# Control.net
KiCad netlist of a schematic drawn in Altium Designer
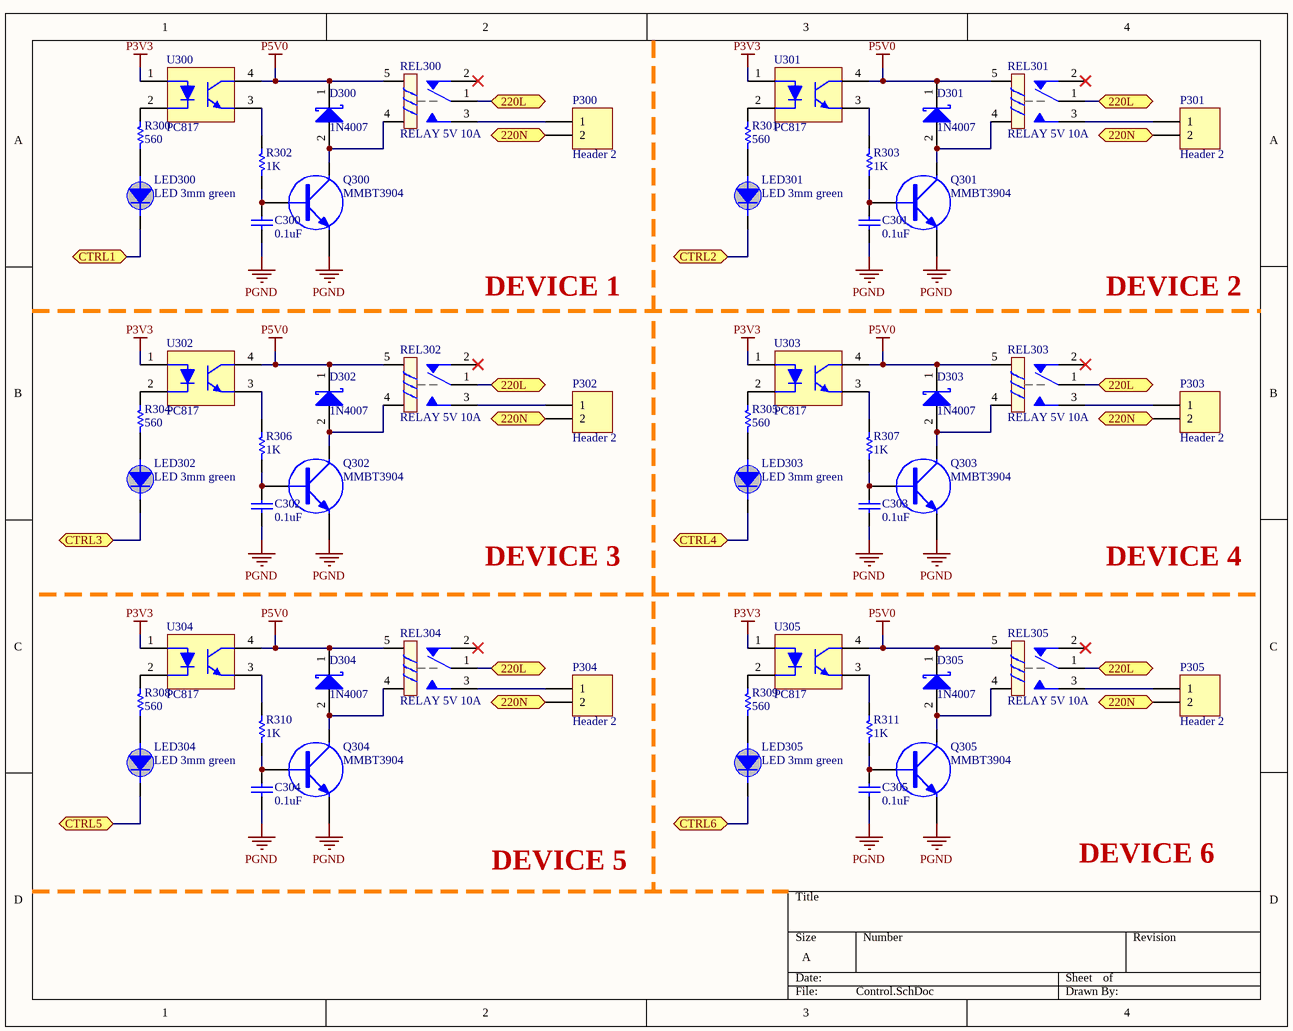
[diagram p0: Control.SchDoc]

(export (version "E")
  (design (tool "Eeschema 10.0.6"))
  (components
    (comp (ref "C300") (value "0.1uF") (footprint "0805 cap") (libsource (lib "BinhLib") (part "cap SMD")))
    (comp (ref "C301") (value "0.1uF") (footprint "0805 cap") (libsource (lib "BinhLib") (part "cap SMD")))
    (comp (ref "C302") (value "0.1uF") (footprint "0805 cap") (libsource (lib "BinhLib") (part "cap SMD")))
    (comp (ref "C303") (value "0.1uF") (footprint "0805 cap") (libsource (lib "BinhLib") (part "cap SMD")))
    (comp (ref "C304") (value "0.1uF") (footprint "0805 cap") (libsource (lib "BinhLib") (part "cap SMD")))
    (comp (ref "C305") (value "0.1uF") (footprint "0805 cap") (libsource (lib "BinhLib") (part "cap SMD")))
    (comp (ref "D300")
      (value "1N4007")
      (footprint "SMA-diode")
      (libsource (lib "BinhLib") (part "Diode Schottky"))
    )
    (comp (ref "D301")
      (value "1N4007")
      (footprint "SMA-diode")
      (libsource (lib "BinhLib") (part "Diode Schottky"))
    )
    (comp (ref "D302")
      (value "1N4007")
      (footprint "SMA-diode")
      (libsource (lib "BinhLib") (part "Diode Schottky"))
    )
    (comp (ref "D303")
      (value "1N4007")
      (footprint "SMA-diode")
      (libsource (lib "BinhLib") (part "Diode Schottky"))
    )
    (comp (ref "D304")
      (value "1N4007")
      (footprint "SMA-diode")
      (libsource (lib "BinhLib") (part "Diode Schottky"))
    )
    (comp (ref "D305")
      (value "1N4007")
      (footprint "SMA-diode")
      (libsource (lib "BinhLib") (part "Diode Schottky"))
    )
    (comp (ref "LED300")
      (value "LED 3mm green")
      (footprint "LED 3mm green")
      (libsource (lib "BinhLib") (part "LED 3mm green"))
    )
    (comp (ref "LED301")
      (value "LED 3mm green")
      (footprint "LED 3mm green")
      (libsource (lib "BinhLib") (part "LED 3mm green"))
    )
    (comp (ref "LED302")
      (value "LED 3mm green")
      (footprint "LED 3mm green")
      (libsource (lib "BinhLib") (part "LED 3mm green"))
    )
    (comp (ref "LED303")
      (value "LED 3mm green")
      (footprint "LED 3mm green")
      (libsource (lib "BinhLib") (part "LED 3mm green"))
    )
    (comp (ref "LED304")
      (value "LED 3mm green")
      (footprint "LED 3mm green")
      (libsource (lib "BinhLib") (part "LED 3mm green"))
    )
    (comp (ref "LED305")
      (value "LED 3mm green")
      (footprint "LED 3mm green")
      (libsource (lib "BinhLib") (part "LED 3mm green"))
    )
    (comp (ref "P300")
      (value "Header 2")
      (footprint "HED2T")
      (description "Header, 2-Pin")
      (fields (field (name "PUBLISHER") "Altium Limited"))
      (libsource (lib "BinhLib") (part "Header 2"))
    )
    (comp (ref "P301")
      (value "Header 2")
      (footprint "HED2T")
      (description "Header, 2-Pin")
      (fields (field (name "PUBLISHER") "Altium Limited"))
      (libsource (lib "BinhLib") (part "Header 2"))
    )
    (comp (ref "P302")
      (value "Header 2")
      (footprint "HED2T")
      (description "Header, 2-Pin")
      (fields (field (name "PUBLISHER") "Altium Limited"))
      (libsource (lib "BinhLib") (part "Header 2"))
    )
    (comp (ref "P303")
      (value "Header 2")
      (footprint "HED2T")
      (description "Header, 2-Pin")
      (fields (field (name "PUBLISHER") "Altium Limited"))
      (libsource (lib "BinhLib") (part "Header 2"))
    )
    (comp (ref "P304")
      (value "Header 2")
      (footprint "HED2T")
      (description "Header, 2-Pin")
      (fields (field (name "PUBLISHER") "Altium Limited"))
      (libsource (lib "BinhLib") (part "Header 2"))
    )
    (comp (ref "P305")
      (value "Header 2")
      (footprint "HED2T")
      (description "Header, 2-Pin")
      (fields (field (name "PUBLISHER") "Altium Limited"))
      (libsource (lib "BinhLib") (part "Header 2"))
    )
    (comp (ref "Q300")
      (value "MMBT3904")
      (footprint "SOT23-3LN")
      (description "TRANS NPN 40V 0.2A SOT-23")
      (fields (field (name "MANUFACTURER") "Fairchild/ON Semiconductor"))
      (libsource (lib "BinhLib") (part "MMBT3904"))
    )
    (comp (ref "Q301")
      (value "MMBT3904")
      (footprint "SOT23-3LN")
      (description "TRANS NPN 40V 0.2A SOT-23")
      (fields (field (name "MANUFACTURER") "Fairchild/ON Semiconductor"))
      (libsource (lib "BinhLib") (part "MMBT3904"))
    )
    (comp (ref "Q302")
      (value "MMBT3904")
      (footprint "SOT23-3LN")
      (description "TRANS NPN 40V 0.2A SOT-23")
      (fields (field (name "MANUFACTURER") "Fairchild/ON Semiconductor"))
      (libsource (lib "BinhLib") (part "MMBT3904"))
    )
    (comp (ref "Q303")
      (value "MMBT3904")
      (footprint "SOT23-3LN")
      (description "TRANS NPN 40V 0.2A SOT-23")
      (fields (field (name "MANUFACTURER") "Fairchild/ON Semiconductor"))
      (libsource (lib "BinhLib") (part "MMBT3904"))
    )
    (comp (ref "Q304")
      (value "MMBT3904")
      (footprint "SOT23-3LN")
      (description "TRANS NPN 40V 0.2A SOT-23")
      (fields (field (name "MANUFACTURER") "Fairchild/ON Semiconductor"))
      (libsource (lib "BinhLib") (part "MMBT3904"))
    )
    (comp (ref "Q305")
      (value "MMBT3904")
      (footprint "SOT23-3LN")
      (description "TRANS NPN 40V 0.2A SOT-23")
      (fields (field (name "MANUFACTURER") "Fairchild/ON Semiconductor"))
      (libsource (lib "BinhLib") (part "MMBT3904"))
    )
    (comp (ref "R300")
      (value "560")
      (footprint "0805 Resistor")
      (libsource (lib "BinhLib") (part "Resistor"))
    )
    (comp (ref "R301")
      (value "560")
      (footprint "0805 Resistor")
      (libsource (lib "BinhLib") (part "Resistor"))
    )
    (comp (ref "R302") (value "1K") (footprint "0805 Resistor") (libsource (lib "BinhLib") (part "Resistor")))
    (comp (ref "R303") (value "1K") (footprint "0805 Resistor") (libsource (lib "BinhLib") (part "Resistor")))
    (comp (ref "R304")
      (value "560")
      (footprint "0805 Resistor")
      (libsource (lib "BinhLib") (part "Resistor"))
    )
    (comp (ref "R305")
      (value "560")
      (footprint "0805 Resistor")
      (libsource (lib "BinhLib") (part "Resistor"))
    )
    (comp (ref "R306") (value "1K") (footprint "0805 Resistor") (libsource (lib "BinhLib") (part "Resistor")))
    (comp (ref "R307") (value "1K") (footprint "0805 Resistor") (libsource (lib "BinhLib") (part "Resistor")))
    (comp (ref "R308")
      (value "560")
      (footprint "0805 Resistor")
      (libsource (lib "BinhLib") (part "Resistor"))
    )
    (comp (ref "R309")
      (value "560")
      (footprint "0805 Resistor")
      (libsource (lib "BinhLib") (part "Resistor"))
    )
    (comp (ref "R310") (value "1K") (footprint "0805 Resistor") (libsource (lib "BinhLib") (part "Resistor")))
    (comp (ref "R311") (value "1K") (footprint "0805 Resistor") (libsource (lib "BinhLib") (part "Resistor")))
    (comp (ref "REL300")
      (value "RELAY 5V 10A")
      (footprint "RELAY 5V-10A")
      (libsource (lib "ThinhNguyenLib") (part "RELAY 5V 10A"))
    )
    (comp (ref "REL301")
      (value "RELAY 5V 10A")
      (footprint "RELAY 5V-10A")
      (libsource (lib "ThinhNguyenLib") (part "RELAY 5V 10A"))
    )
    (comp (ref "REL302")
      (value "RELAY 5V 10A")
      (footprint "RELAY 5V-10A")
      (libsource (lib "ThinhNguyenLib") (part "RELAY 5V 10A"))
    )
    (comp (ref "REL303")
      (value "RELAY 5V 10A")
      (footprint "RELAY 5V-10A")
      (libsource (lib "ThinhNguyenLib") (part "RELAY 5V 10A"))
    )
    (comp (ref "REL304")
      (value "RELAY 5V 10A")
      (footprint "RELAY 5V-10A")
      (libsource (lib "ThinhNguyenLib") (part "RELAY 5V 10A"))
    )
    (comp (ref "REL305")
      (value "RELAY 5V 10A")
      (footprint "RELAY 5V-10A")
      (libsource (lib "ThinhNguyenLib") (part "RELAY 5V 10A"))
    )
    (comp (ref "U300") (value "PC817") (footprint "PC817 SMD") (libsource (lib "BinhLib") (part "PC817")))
    (comp (ref "U301") (value "PC817") (footprint "PC817 SMD") (libsource (lib "BinhLib") (part "PC817")))
    (comp (ref "U302") (value "PC817") (footprint "PC817 SMD") (libsource (lib "BinhLib") (part "PC817")))
    (comp (ref "U303") (value "PC817") (footprint "PC817 SMD") (libsource (lib "BinhLib") (part "PC817")))
    (comp (ref "U304") (value "PC817") (footprint "PC817 SMD") (libsource (lib "BinhLib") (part "PC817")))
    (comp (ref "U305") (value "PC817") (footprint "PC817 SMD") (libsource (lib "BinhLib") (part "PC817")))
  )
  (nets
    (net (code "1") (name "/220L") (class "Default")
      (node (ref "REL300") (pin "1") (pinfunction "1_1") (pintype "passive"))
      (node (ref "REL301") (pin "1") (pinfunction "1_1") (pintype "passive"))
      (node (ref "REL302") (pin "1") (pinfunction "1_1") (pintype "passive"))
      (node (ref "REL303") (pin "1") (pinfunction "1_1") (pintype "passive"))
      (node (ref "REL304") (pin "1") (pinfunction "1_1") (pintype "passive"))
      (node (ref "REL305") (pin "1") (pinfunction "1_1") (pintype "passive"))
    )
    (net (code "2") (name "/220N") (class "Default")
      (node (ref "P300") (pin "2") (pinfunction "2_2") (pintype "passive"))
      (node (ref "P301") (pin "2") (pinfunction "2_2") (pintype "passive"))
      (node (ref "P302") (pin "2") (pinfunction "2_2") (pintype "passive"))
      (node (ref "P303") (pin "2") (pinfunction "2_2") (pintype "passive"))
      (node (ref "P304") (pin "2") (pinfunction "2_2") (pintype "passive"))
      (node (ref "P305") (pin "2") (pinfunction "2_2") (pintype "passive"))
    )
    (net (code "3") (name "/CTRL1") (class "Default")
      (node (ref "LED300") (pin "2") (pinfunction "Katot_2") (pintype "passive"))
    )
    (net (code "4") (name "/CTRL2") (class "Default")
      (node (ref "LED301") (pin "2") (pinfunction "Katot_2") (pintype "passive"))
    )
    (net (code "5") (name "/CTRL3") (class "Default")
      (node (ref "LED302") (pin "2") (pinfunction "Katot_2") (pintype "passive"))
    )
    (net (code "6") (name "/CTRL4") (class "Default")
      (node (ref "LED303") (pin "2") (pinfunction "Katot_2") (pintype "passive"))
    )
    (net (code "7") (name "/CTRL5") (class "Default")
      (node (ref "LED304") (pin "2") (pinfunction "Katot_2") (pintype "passive"))
    )
    (net (code "8") (name "/CTRL6") (class "Default")
      (node (ref "LED305") (pin "2") (pinfunction "Katot_2") (pintype "passive"))
    )
    (net (code "9") (name "Net-(D300-A)") (class "Default")
      (node (ref "D300") (pin "2") (pinfunction "A_2") (pintype "passive"))
      (node (ref "Q300") (pin "2") (pinfunction "C_2") (pintype "passive"))
      (node (ref "REL300") (pin "4") (pinfunction "4_4") (pintype "passive"))
    )
    (net (code "10") (name "Net-(D301-A)") (class "Default")
      (node (ref "D301") (pin "2") (pinfunction "A_2") (pintype "passive"))
      (node (ref "Q301") (pin "2") (pinfunction "C_2") (pintype "passive"))
      (node (ref "REL301") (pin "4") (pinfunction "4_4") (pintype "passive"))
    )
    (net (code "11") (name "Net-(D302-A)") (class "Default")
      (node (ref "D302") (pin "2") (pinfunction "A_2") (pintype "passive"))
      (node (ref "Q302") (pin "2") (pinfunction "C_2") (pintype "passive"))
      (node (ref "REL302") (pin "4") (pinfunction "4_4") (pintype "passive"))
    )
    (net (code "12") (name "Net-(D303-A)") (class "Default")
      (node (ref "D303") (pin "2") (pinfunction "A_2") (pintype "passive"))
      (node (ref "Q303") (pin "2") (pinfunction "C_2") (pintype "passive"))
      (node (ref "REL303") (pin "4") (pinfunction "4_4") (pintype "passive"))
    )
    (net (code "13") (name "Net-(D304-A)") (class "Default")
      (node (ref "D304") (pin "2") (pinfunction "A_2") (pintype "passive"))
      (node (ref "Q304") (pin "2") (pinfunction "C_2") (pintype "passive"))
      (node (ref "REL304") (pin "4") (pinfunction "4_4") (pintype "passive"))
    )
    (net (code "14") (name "Net-(D305-A)") (class "Default")
      (node (ref "D305") (pin "2") (pinfunction "A_2") (pintype "passive"))
      (node (ref "Q305") (pin "2") (pinfunction "C_2") (pintype "passive"))
      (node (ref "REL305") (pin "4") (pinfunction "4_4") (pintype "passive"))
    )
    (net (code "15") (name "Net-(LED300-anot)") (class "Default")
      (node (ref "LED300") (pin "1") (pinfunction "anot_1") (pintype "passive"))
      (node (ref "R300") (pin "2") (pinfunction "2_2") (pintype "passive"))
    )
    (net (code "16") (name "Net-(LED301-anot)") (class "Default")
      (node (ref "LED301") (pin "1") (pinfunction "anot_1") (pintype "passive"))
      (node (ref "R301") (pin "2") (pinfunction "2_2") (pintype "passive"))
    )
    (net (code "17") (name "Net-(LED302-anot)") (class "Default")
      (node (ref "LED302") (pin "1") (pinfunction "anot_1") (pintype "passive"))
      (node (ref "R304") (pin "2") (pinfunction "2_2") (pintype "passive"))
    )
    (net (code "18") (name "Net-(LED303-anot)") (class "Default")
      (node (ref "LED303") (pin "1") (pinfunction "anot_1") (pintype "passive"))
      (node (ref "R305") (pin "2") (pinfunction "2_2") (pintype "passive"))
    )
    (net (code "19") (name "Net-(LED304-anot)") (class "Default")
      (node (ref "LED304") (pin "1") (pinfunction "anot_1") (pintype "passive"))
      (node (ref "R308") (pin "2") (pinfunction "2_2") (pintype "passive"))
    )
    (net (code "20") (name "Net-(LED305-anot)") (class "Default")
      (node (ref "LED305") (pin "1") (pinfunction "anot_1") (pintype "passive"))
      (node (ref "R309") (pin "2") (pinfunction "2_2") (pintype "passive"))
    )
    (net (code "21") (name "Net-(P300-Pad1)") (class "Default")
      (node (ref "P300") (pin "1") (pinfunction "1_1") (pintype "passive"))
      (node (ref "REL300") (pin "3") (pinfunction "3_3") (pintype "passive"))
    )
    (net (code "22") (name "Net-(P301-Pad1)") (class "Default")
      (node (ref "P301") (pin "1") (pinfunction "1_1") (pintype "passive"))
      (node (ref "REL301") (pin "3") (pinfunction "3_3") (pintype "passive"))
    )
    (net (code "23") (name "Net-(P302-Pad1)") (class "Default")
      (node (ref "P302") (pin "1") (pinfunction "1_1") (pintype "passive"))
      (node (ref "REL302") (pin "3") (pinfunction "3_3") (pintype "passive"))
    )
    (net (code "24") (name "Net-(P303-Pad1)") (class "Default")
      (node (ref "P303") (pin "1") (pinfunction "1_1") (pintype "passive"))
      (node (ref "REL303") (pin "3") (pinfunction "3_3") (pintype "passive"))
    )
    (net (code "25") (name "Net-(P304-Pad1)") (class "Default")
      (node (ref "P304") (pin "1") (pinfunction "1_1") (pintype "passive"))
      (node (ref "REL304") (pin "3") (pinfunction "3_3") (pintype "passive"))
    )
    (net (code "26") (name "Net-(P305-Pad1)") (class "Default")
      (node (ref "P305") (pin "1") (pinfunction "1_1") (pintype "passive"))
      (node (ref "REL305") (pin "3") (pinfunction "3_3") (pintype "passive"))
    )
    (net (code "27") (name "Net-(Q300-B)") (class "Default")
      (node (ref "C300") (pin "2") (pintype "passive"))
      (node (ref "Q300") (pin "1") (pinfunction "B_1") (pintype "passive"))
      (node (ref "R302") (pin "2") (pinfunction "2_2") (pintype "passive"))
    )
    (net (code "28") (name "Net-(Q301-B)") (class "Default")
      (node (ref "C301") (pin "2") (pintype "passive"))
      (node (ref "Q301") (pin "1") (pinfunction "B_1") (pintype "passive"))
      (node (ref "R303") (pin "2") (pinfunction "2_2") (pintype "passive"))
    )
    (net (code "29") (name "Net-(Q302-B)") (class "Default")
      (node (ref "C302") (pin "2") (pintype "passive"))
      (node (ref "Q302") (pin "1") (pinfunction "B_1") (pintype "passive"))
      (node (ref "R306") (pin "2") (pinfunction "2_2") (pintype "passive"))
    )
    (net (code "30") (name "Net-(Q303-B)") (class "Default")
      (node (ref "C303") (pin "2") (pintype "passive"))
      (node (ref "Q303") (pin "1") (pinfunction "B_1") (pintype "passive"))
      (node (ref "R307") (pin "2") (pinfunction "2_2") (pintype "passive"))
    )
    (net (code "31") (name "Net-(Q304-B)") (class "Default")
      (node (ref "C304") (pin "2") (pintype "passive"))
      (node (ref "Q304") (pin "1") (pinfunction "B_1") (pintype "passive"))
      (node (ref "R310") (pin "2") (pinfunction "2_2") (pintype "passive"))
    )
    (net (code "32") (name "Net-(Q305-B)") (class "Default")
      (node (ref "C305") (pin "2") (pintype "passive"))
      (node (ref "Q305") (pin "1") (pinfunction "B_1") (pintype "passive"))
      (node (ref "R311") (pin "2") (pinfunction "2_2") (pintype "passive"))
    )
    (net (code "33") (name "Net-(R300-Pad1)") (class "Default")
      (node (ref "R300") (pin "1") (pinfunction "1_1") (pintype "passive"))
      (node (ref "U300") (pin "2") (pinfunction "2_2") (pintype "passive"))
    )
    (net (code "34") (name "Net-(R301-Pad1)") (class "Default")
      (node (ref "R301") (pin "1") (pinfunction "1_1") (pintype "passive"))
      (node (ref "U301") (pin "2") (pinfunction "2_2") (pintype "passive"))
    )
    (net (code "35") (name "Net-(R302-Pad1)") (class "Default")
      (node (ref "R302") (pin "1") (pinfunction "1_1") (pintype "passive"))
      (node (ref "U300") (pin "3") (pinfunction "3_3") (pintype "passive"))
    )
    (net (code "36") (name "Net-(R303-Pad1)") (class "Default")
      (node (ref "R303") (pin "1") (pinfunction "1_1") (pintype "passive"))
      (node (ref "U301") (pin "3") (pinfunction "3_3") (pintype "passive"))
    )
    (net (code "37") (name "Net-(R304-Pad1)") (class "Default")
      (node (ref "R304") (pin "1") (pinfunction "1_1") (pintype "passive"))
      (node (ref "U302") (pin "2") (pinfunction "2_2") (pintype "passive"))
    )
    (net (code "38") (name "Net-(R305-Pad1)") (class "Default")
      (node (ref "R305") (pin "1") (pinfunction "1_1") (pintype "passive"))
      (node (ref "U303") (pin "2") (pinfunction "2_2") (pintype "passive"))
    )
    (net (code "39") (name "Net-(R306-Pad1)") (class "Default")
      (node (ref "R306") (pin "1") (pinfunction "1_1") (pintype "passive"))
      (node (ref "U302") (pin "3") (pinfunction "3_3") (pintype "passive"))
    )
    (net (code "40") (name "Net-(R307-Pad1)") (class "Default")
      (node (ref "R307") (pin "1") (pinfunction "1_1") (pintype "passive"))
      (node (ref "U303") (pin "3") (pinfunction "3_3") (pintype "passive"))
    )
    (net (code "41") (name "Net-(R308-Pad1)") (class "Default")
      (node (ref "R308") (pin "1") (pinfunction "1_1") (pintype "passive"))
      (node (ref "U304") (pin "2") (pinfunction "2_2") (pintype "passive"))
    )
    (net (code "42") (name "Net-(R309-Pad1)") (class "Default")
      (node (ref "R309") (pin "1") (pinfunction "1_1") (pintype "passive"))
      (node (ref "U305") (pin "2") (pinfunction "2_2") (pintype "passive"))
    )
    (net (code "43") (name "Net-(R310-Pad1)") (class "Default")
      (node (ref "R310") (pin "1") (pinfunction "1_1") (pintype "passive"))
      (node (ref "U304") (pin "3") (pinfunction "3_3") (pintype "passive"))
    )
    (net (code "44") (name "Net-(R311-Pad1)") (class "Default")
      (node (ref "R311") (pin "1") (pinfunction "1_1") (pintype "passive"))
      (node (ref "U305") (pin "3") (pinfunction "3_3") (pintype "passive"))
    )
    (net (code "45") (name "P3V3") (class "Default")
      (node (ref "U300") (pin "1") (pinfunction "1_1") (pintype "passive"))
      (node (ref "U301") (pin "1") (pinfunction "1_1") (pintype "passive"))
      (node (ref "U302") (pin "1") (pinfunction "1_1") (pintype "passive"))
      (node (ref "U303") (pin "1") (pinfunction "1_1") (pintype "passive"))
      (node (ref "U304") (pin "1") (pinfunction "1_1") (pintype "passive"))
      (node (ref "U305") (pin "1") (pinfunction "1_1") (pintype "passive"))
    )
    (net (code "46") (name "P5V0") (class "Default")
      (node (ref "D300") (pin "1") (pinfunction "K_1") (pintype "passive"))
      (node (ref "D301") (pin "1") (pinfunction "K_1") (pintype "passive"))
      (node (ref "D302") (pin "1") (pinfunction "K_1") (pintype "passive"))
      (node (ref "D303") (pin "1") (pinfunction "K_1") (pintype "passive"))
      (node (ref "D304") (pin "1") (pinfunction "K_1") (pintype "passive"))
      (node (ref "D305") (pin "1") (pinfunction "K_1") (pintype "passive"))
      (node (ref "REL300") (pin "5") (pinfunction "5_5") (pintype "passive"))
      (node (ref "REL301") (pin "5") (pinfunction "5_5") (pintype "passive"))
      (node (ref "REL302") (pin "5") (pinfunction "5_5") (pintype "passive"))
      (node (ref "REL303") (pin "5") (pinfunction "5_5") (pintype "passive"))
      (node (ref "REL304") (pin "5") (pinfunction "5_5") (pintype "passive"))
      (node (ref "REL305") (pin "5") (pinfunction "5_5") (pintype "passive"))
      (node (ref "U300") (pin "4") (pinfunction "4_4") (pintype "passive"))
      (node (ref "U301") (pin "4") (pinfunction "4_4") (pintype "passive"))
      (node (ref "U302") (pin "4") (pinfunction "4_4") (pintype "passive"))
      (node (ref "U303") (pin "4") (pinfunction "4_4") (pintype "passive"))
      (node (ref "U304") (pin "4") (pinfunction "4_4") (pintype "passive"))
      (node (ref "U305") (pin "4") (pinfunction "4_4") (pintype "passive"))
    )
    (net (code "47") (name "PGND") (class "Default")
      (node (ref "C300") (pin "1") (pintype "passive"))
      (node (ref "C301") (pin "1") (pintype "passive"))
      (node (ref "C302") (pin "1") (pintype "passive"))
      (node (ref "C303") (pin "1") (pintype "passive"))
      (node (ref "C304") (pin "1") (pintype "passive"))
      (node (ref "C305") (pin "1") (pintype "passive"))
      (node (ref "Q300") (pin "3") (pinfunction "E_3") (pintype "passive"))
      (node (ref "Q301") (pin "3") (pinfunction "E_3") (pintype "passive"))
      (node (ref "Q302") (pin "3") (pinfunction "E_3") (pintype "passive"))
      (node (ref "Q303") (pin "3") (pinfunction "E_3") (pintype "passive"))
      (node (ref "Q304") (pin "3") (pinfunction "E_3") (pintype "passive"))
      (node (ref "Q305") (pin "3") (pinfunction "E_3") (pintype "passive"))
    )
    (net (code "48") (name "unconnected-(REL300-Pad2)") (class "Default")
      (node (ref "REL300") (pin "2") (pinfunction "2_2") (pintype "passive+no_connect"))
    )
    (net (code "49") (name "unconnected-(REL301-Pad2)") (class "Default")
      (node (ref "REL301") (pin "2") (pinfunction "2_2") (pintype "passive+no_connect"))
    )
    (net (code "50") (name "unconnected-(REL302-Pad2)") (class "Default")
      (node (ref "REL302") (pin "2") (pinfunction "2_2") (pintype "passive+no_connect"))
    )
    (net (code "51") (name "unconnected-(REL303-Pad2)") (class "Default")
      (node (ref "REL303") (pin "2") (pinfunction "2_2") (pintype "passive+no_connect"))
    )
    (net (code "52") (name "unconnected-(REL304-Pad2)") (class "Default")
      (node (ref "REL304") (pin "2") (pinfunction "2_2") (pintype "passive+no_connect"))
    )
    (net (code "53") (name "unconnected-(REL305-Pad2)") (class "Default")
      (node (ref "REL305") (pin "2") (pinfunction "2_2") (pintype "passive+no_connect"))
    )
  )
)
